# sfm3300_adapter.net
KiCad netlist of a schematic drawn in EAGLE
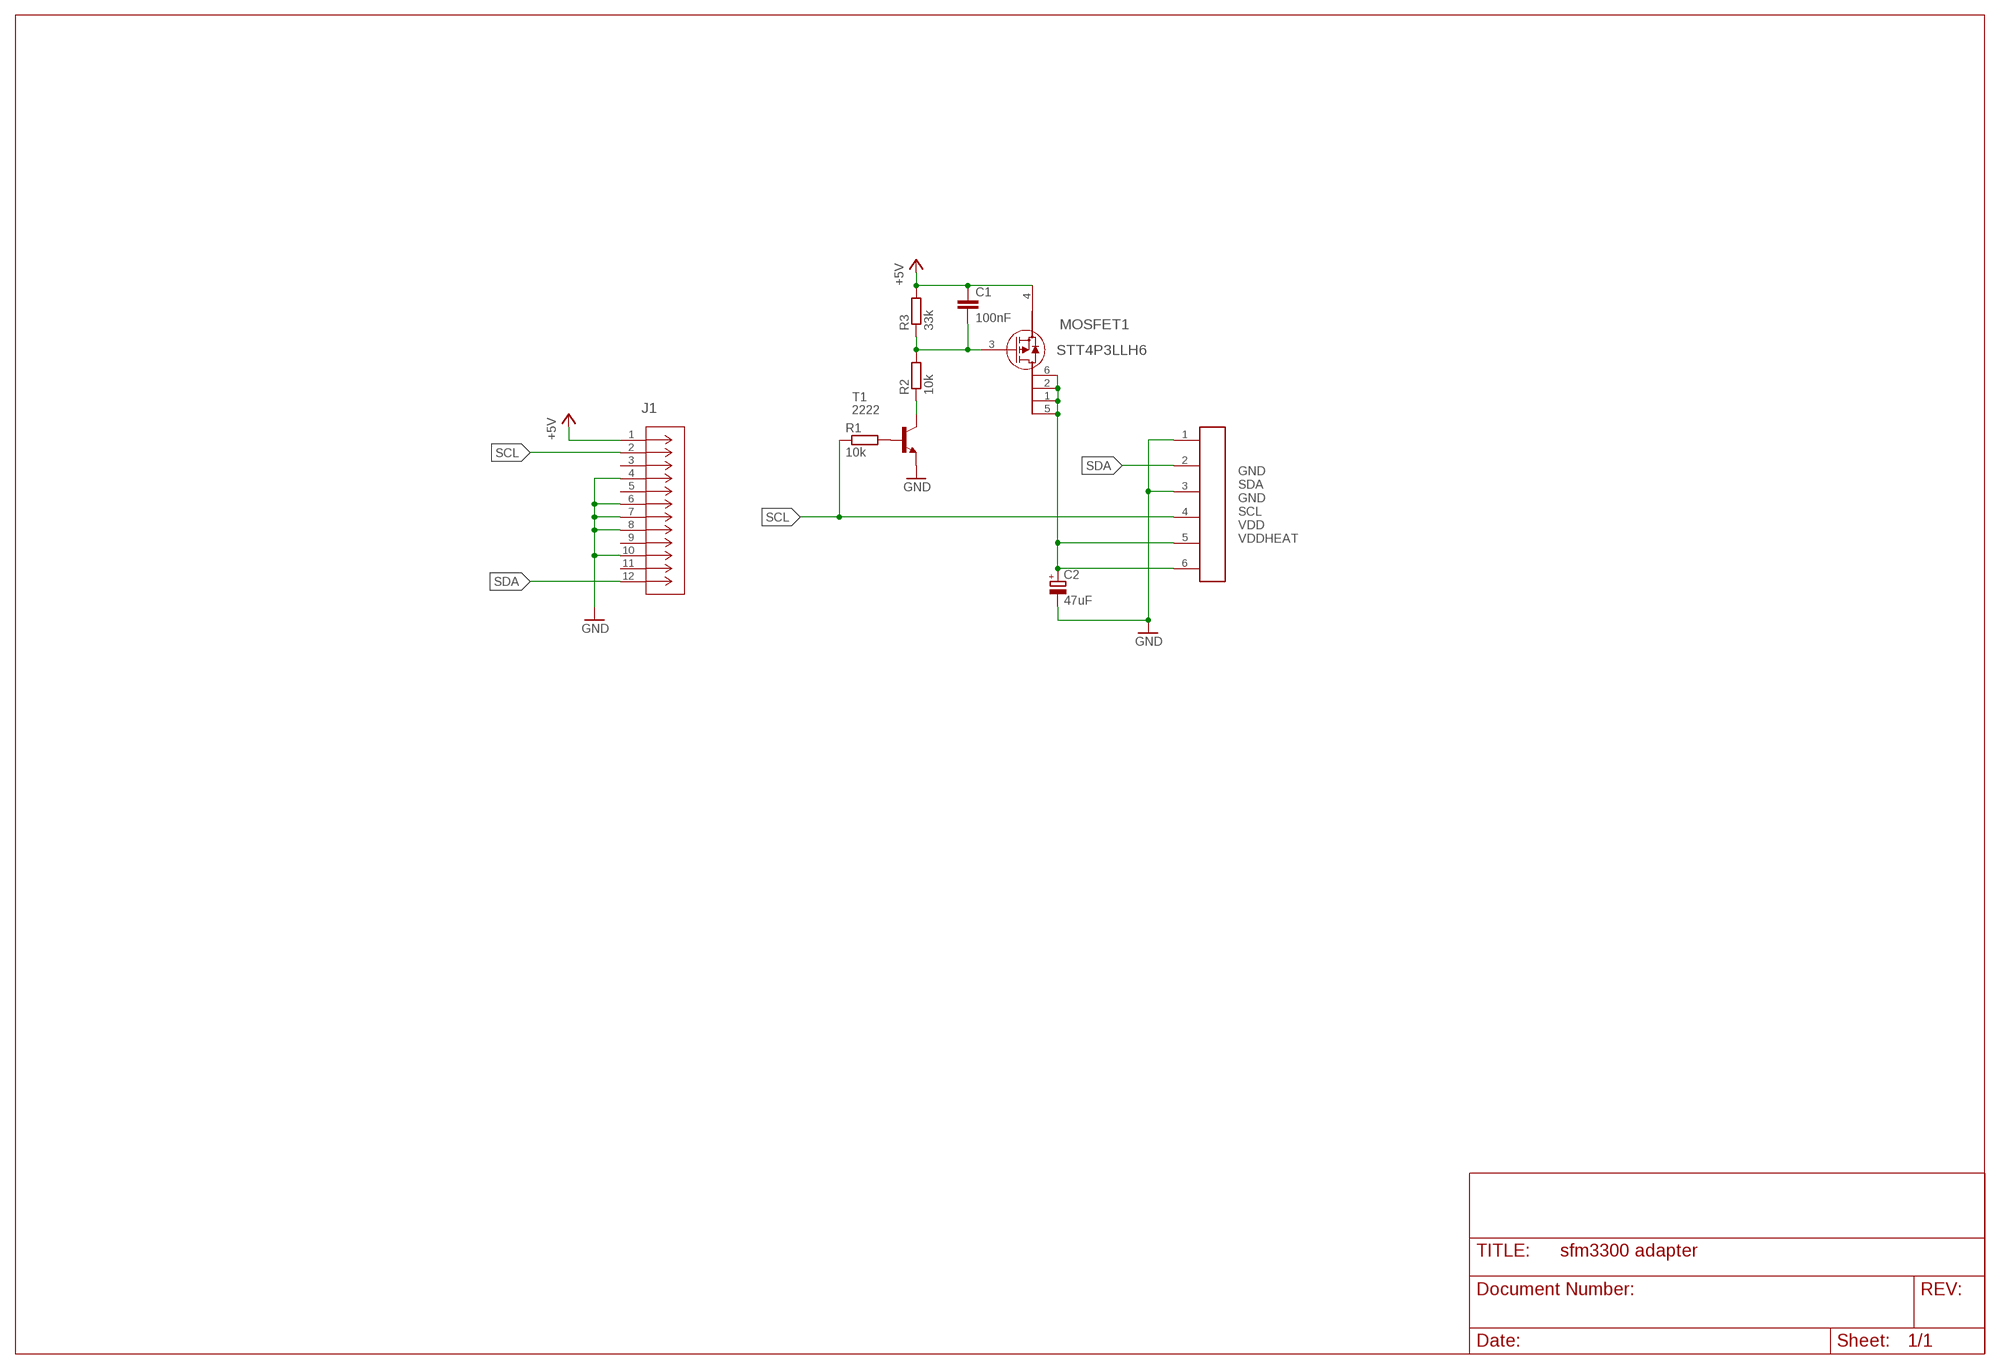
[diagram p0: schematic, sheet 1]

(export (version "E")
  (design (tool "Eeschema 10.0.6"))
  (components
    (comp (ref "C1")
      (value "100nF")
      (footprint "eagle-import:C0603")
      (libsource (lib "eagle-import") (part "C-EUC0603"))
    )
    (comp (ref "C2")
      (value "47uF")
      (footprint "eagle-import:SMC_A")
      (libsource (lib "eagle-import") (part "CPOL-EUSMCA"))
    )
    (comp (ref "J1")
      (value "1-188275-2")
      (footprint "eagle-import:CONN_1-188275-2_TYC")
      (fields (field (name "COPYRIGHT") "Copyright (C) 2016 Accelerated Designs. All rights reserved"))
      (libsource (lib "eagle-import") (part "1-188275-2"))
    )
    (comp (ref "MOSFET1")
      (value "STT4P3LLH6")
      (footprint "eagle-import:SOT23-6L_STM")
      (fields (field (name "COPYRIGHT") "Copyright (C) 2018 Accelerated Designs. All rights reserved"))
      (libsource (lib "eagle-import") (part "STT4P3LLH6"))
    )
    (comp (ref "R1")
      (value "10k")
      (footprint "eagle-import:R0603")
      (libsource (lib "eagle-import") (part "R-EU_R0603"))
    )
    (comp (ref "R2")
      (value "10k")
      (footprint "eagle-import:R0603")
      (libsource (lib "eagle-import") (part "R-EU_R0603"))
    )
    (comp (ref "R3")
      (value "33k")
      (footprint "eagle-import:R0603")
      (libsource (lib "eagle-import") (part "R-EU_R0603"))
    )
    (comp (ref "T1")
      (value "2222")
      (footprint "eagle-import:SOT23-BEC")
      (libsource (lib "eagle-import") (part "-NPN-SOT23-BECMMBT2222ALT1"))
    )
    (comp (ref "U$1")
      (value "SPRING6")
      (footprint "eagle-import:SPRING-6")
      (libsource (lib "eagle-import") (part "SPRING6"))
    )
  )
  (nets
    (net (code "1") (name "+5V") (class "Default")
      (node (ref "C1") (pin "1") (pinfunction "1_1") (pintype "passive"))
      (node (ref "J1") (pin "1") (pinfunction "1_1") (pintype "passive"))
      (node (ref "MOSFET1") (pin "4") (pinfunction "4_4") (pintype "passive"))
      (node (ref "R3") (pin "2") (pinfunction "2_2") (pintype "passive"))
    )
    (net (code "2") (name "GND") (class "Default")
      (node (ref "C2") (pin "-") (pinfunction "-_-") (pintype "passive"))
      (node (ref "J1") (pin "10") (pinfunction "10_10") (pintype "passive"))
      (node (ref "J1") (pin "4") (pinfunction "4_4") (pintype "passive"))
      (node (ref "J1") (pin "6") (pinfunction "6_6") (pintype "passive"))
      (node (ref "J1") (pin "7") (pinfunction "7_7") (pintype "passive"))
      (node (ref "J1") (pin "8") (pinfunction "8_8") (pintype "passive"))
      (node (ref "T1") (pin "E") (pinfunction "E_E") (pintype "passive"))
      (node (ref "U$1") (pin "1") (pinfunction "1_1") (pintype "passive"))
      (node (ref "U$1") (pin "3") (pinfunction "3_3") (pintype "passive"))
    )
    (net (code "3") (name "Net-(C1-Pad2)") (class "Default")
      (node (ref "C1") (pin "2") (pinfunction "2_2") (pintype "passive"))
      (node (ref "MOSFET1") (pin "3") (pinfunction "3_3") (pintype "passive"))
      (node (ref "R2") (pin "2") (pinfunction "2_2") (pintype "passive"))
      (node (ref "R3") (pin "1") (pinfunction "1_1") (pintype "passive"))
    )
    (net (code "4") (name "Net-(C2-Pad+)") (class "Default")
      (node (ref "C2") (pin "+") (pinfunction "+_+") (pintype "passive"))
      (node (ref "MOSFET1") (pin "1") (pinfunction "1_1") (pintype "passive"))
      (node (ref "MOSFET1") (pin "2") (pinfunction "2_2") (pintype "passive"))
      (node (ref "MOSFET1") (pin "5") (pinfunction "5_5") (pintype "passive"))
      (node (ref "MOSFET1") (pin "6") (pinfunction "6_6") (pintype "passive"))
      (node (ref "U$1") (pin "5") (pinfunction "5_5") (pintype "passive"))
      (node (ref "U$1") (pin "6") (pinfunction "6_6") (pintype "passive"))
    )
    (net (code "5") (name "Net-(R1-Pad2)") (class "Default")
      (node (ref "R1") (pin "2") (pinfunction "2_2") (pintype "passive"))
      (node (ref "T1") (pin "B") (pinfunction "B_B") (pintype "passive"))
    )
    (net (code "6") (name "Net-(R2-Pad1)") (class "Default")
      (node (ref "R2") (pin "1") (pinfunction "1_1") (pintype "passive"))
      (node (ref "T1") (pin "C") (pinfunction "C_C") (pintype "passive"))
    )
    (net (code "7") (name "SCL") (class "Default")
      (node (ref "J1") (pin "2") (pinfunction "2_2") (pintype "passive"))
      (node (ref "R1") (pin "1") (pinfunction "1_1") (pintype "passive"))
      (node (ref "U$1") (pin "4") (pinfunction "4_4") (pintype "passive"))
    )
    (net (code "8") (name "SDA") (class "Default")
      (node (ref "J1") (pin "12") (pinfunction "12_12") (pintype "passive"))
      (node (ref "U$1") (pin "2") (pinfunction "2_2") (pintype "passive"))
    )
    (net (code "9") (name "unconnected-(J1-Pad3)") (class "Default")
      (node (ref "J1") (pin "3") (pinfunction "3_3") (pintype "passive"))
    )
    (net (code "10") (name "unconnected-(J1-Pad5)") (class "Default")
      (node (ref "J1") (pin "5") (pinfunction "5_5") (pintype "passive"))
    )
    (net (code "11") (name "unconnected-(J1-Pad9)") (class "Default")
      (node (ref "J1") (pin "9") (pinfunction "9_9") (pintype "passive"))
    )
    (net (code "12") (name "unconnected-(J1-Pad11)") (class "Default")
      (node (ref "J1") (pin "11") (pinfunction "11_11") (pintype "passive"))
    )
  )
)
